# FilterBoard_Schematic.net
KiCad netlist of a schematic drawn in Altium Designer
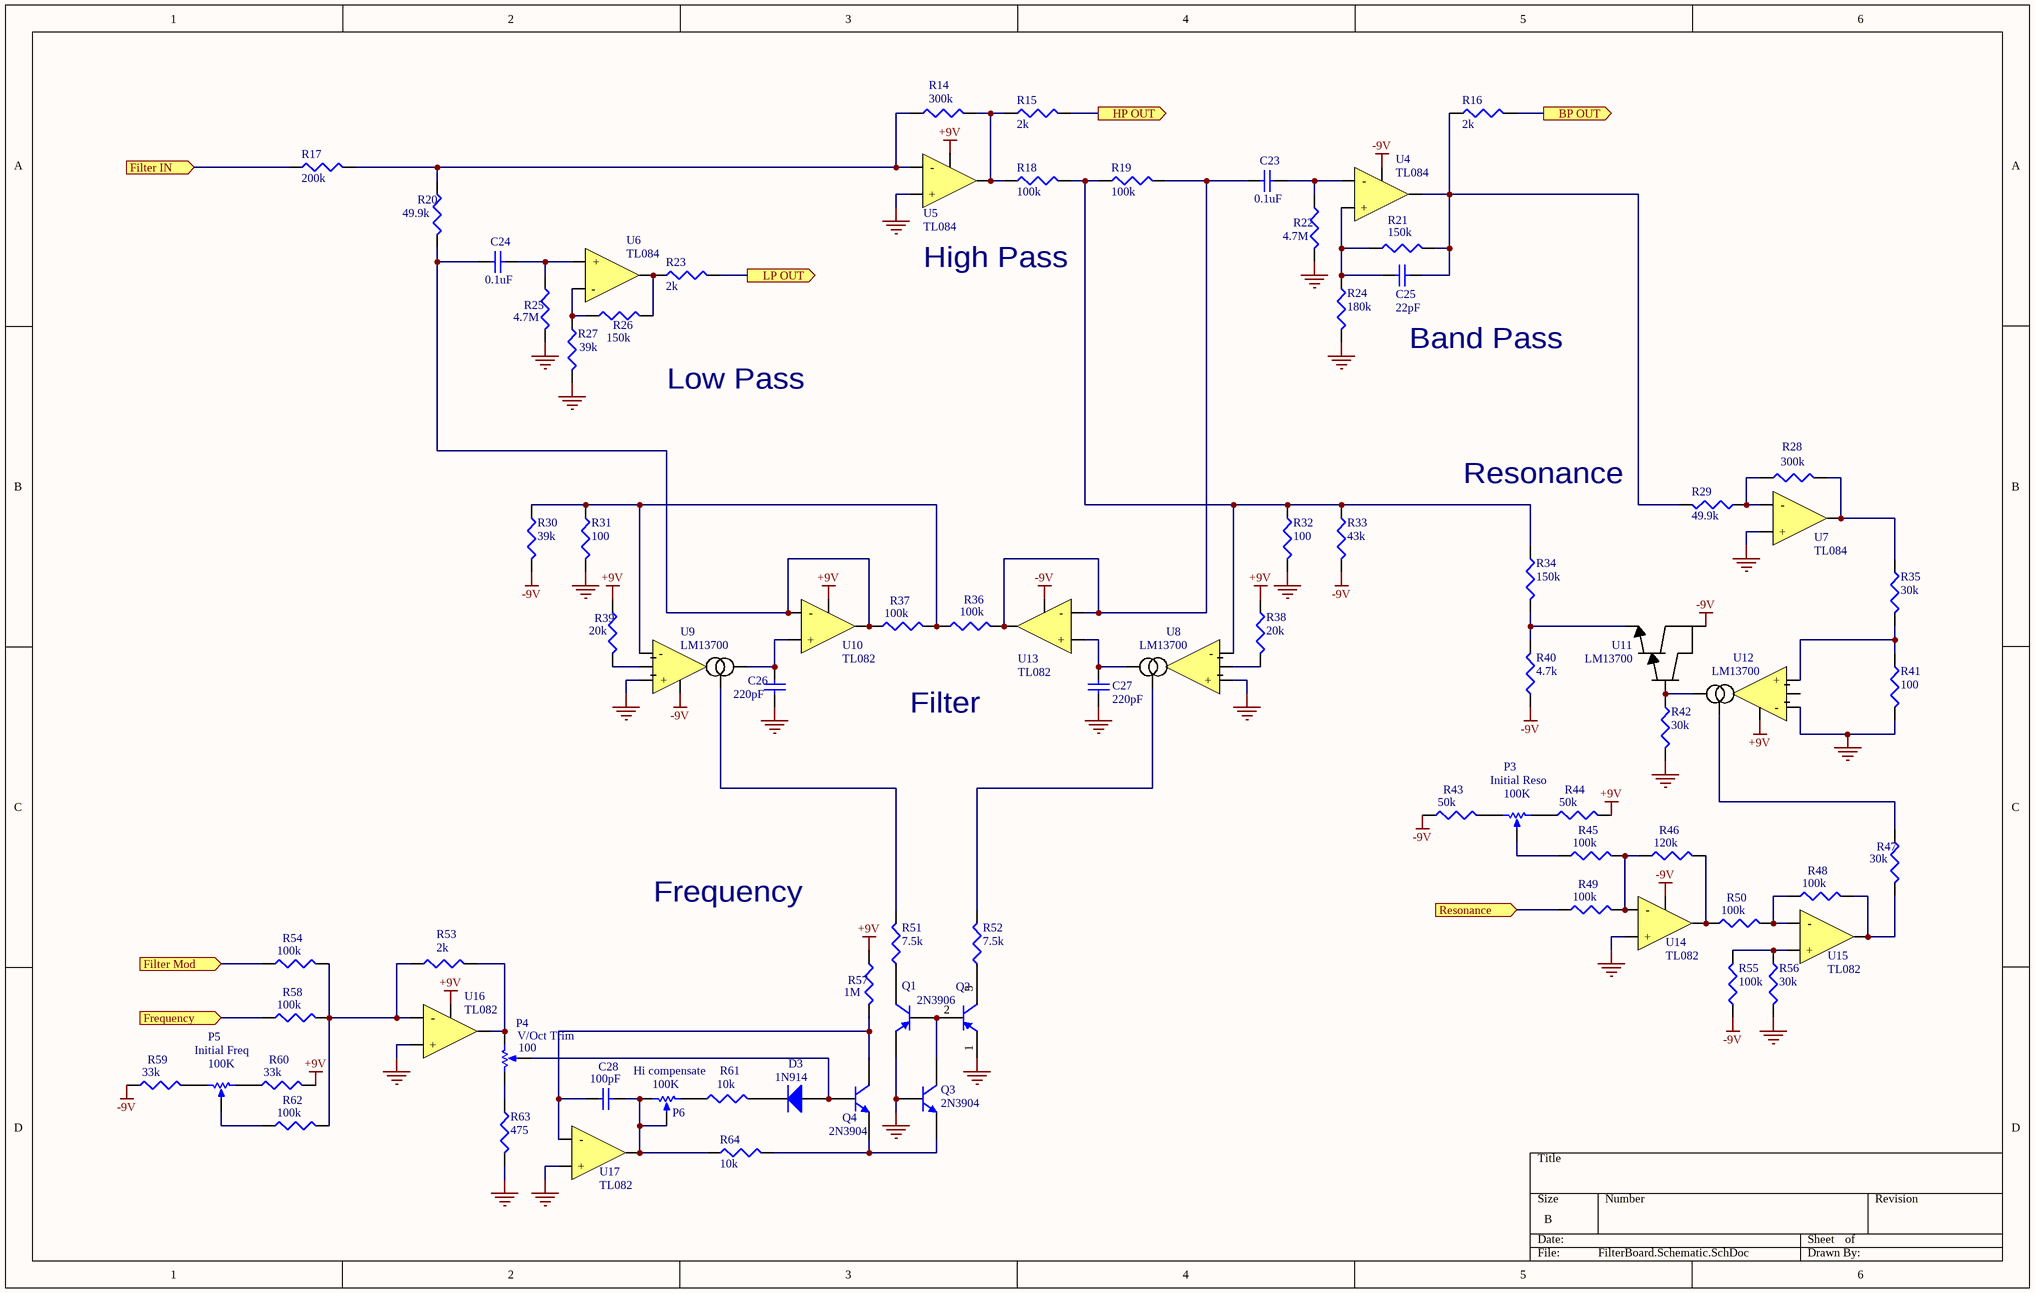
[diagram p0: FilterBoard.Schematic.SchDoc]

(export (version "E")
  (design (tool "Eeschema 10.0.6"))
  (components
    (comp (ref "C23")
      (value "0.1uF")
      (footprint "CAPC1608N")
      (description "Capacitor (Semiconductor SIM Model)")
      (fields (field (name "PUBLISHER") "Altium Limited"))
      (libsource (lib "Miscellaneous Devices") (part "Cap Semi"))
    )
    (comp (ref "C24")
      (value "0.1uF")
      (footprint "CAPC1608N")
      (description "Capacitor (Semiconductor SIM Model)")
      (fields (field (name "PUBLISHER") "Altium Limited"))
      (libsource (lib "Miscellaneous Devices") (part "Cap Semi"))
    )
    (comp (ref "C25")
      (value "22pF")
      (footprint "CAPC1608N")
      (description "Capacitor (Semiconductor SIM Model)")
      (fields (field (name "PUBLISHER") "Altium Limited"))
      (libsource (lib "Miscellaneous Devices") (part "Cap Semi"))
    )
    (comp (ref "C26")
      (value "220pF")
      (footprint "CAPC1608N")
      (description "Capacitor (Semiconductor SIM Model)")
      (fields (field (name "PUBLISHER") "Altium Limited"))
      (libsource (lib "Miscellaneous Devices") (part "Cap Semi"))
    )
    (comp (ref "C27")
      (value "220pF")
      (footprint "CAPC1608N")
      (description "Capacitor (Semiconductor SIM Model)")
      (fields (field (name "PUBLISHER") "Altium Limited"))
      (libsource (lib "Miscellaneous Devices") (part "Cap Semi"))
    )
    (comp (ref "C28")
      (value "100pF")
      (footprint "CAPC1608N")
      (description "Capacitor (Semiconductor SIM Model)")
      (fields (field (name "PUBLISHER") "Altium Limited"))
      (libsource (lib "Miscellaneous Devices") (part "Cap Semi"))
    )
    (comp (ref "D3")
      (value "1N914")
      (footprint "1N914")
      (description "1 Amp General Purpose Rectifier")
      (fields (field (name "PUBLISHER") "Altium Limited"))
      (libsource (lib "Miscellaneous Devices") (part "Diode 1N4001"))
    )
    (comp (ref "P3")
      (value "Initial Reso")
      (footprint "BOURNS Trim pot")
      (description "Potentiometer")
      (fields (field (name "ALTIUM_VALUE") "100K") (field (name "PUBLISHER") "Altium Limited"))
      (libsource (lib "Miscellaneous Devices") (part "RPot"))
    )
    (comp (ref "P4")
      (value "V/Oct Trim")
      (footprint "BOURNS Trim pot")
      (description "Potentiometer")
      (fields (field (name "ALTIUM_VALUE") "100") (field (name "PUBLISHER") "Altium Limited"))
      (libsource (lib "Miscellaneous Devices") (part "RPot"))
    )
    (comp (ref "P5")
      (value "Initial Freq")
      (footprint "BOURNS Trim pot")
      (description "Potentiometer")
      (fields (field (name "ALTIUM_VALUE") "100K") (field (name "PUBLISHER") "Altium Limited"))
      (libsource (lib "Miscellaneous Devices") (part "RPot"))
    )
    (comp (ref "P6")
      (value "Hi compensate")
      (footprint "BOURNS Trim pot")
      (description "Potentiometer")
      (fields (field (name "ALTIUM_VALUE") "100K") (field (name "PUBLISHER") "Altium Limited"))
      (libsource (lib "Miscellaneous Devices") (part "RPot"))
    )
    (comp (ref "Q1")
      (value "2N3906")
      (footprint "2N3906")
      (description "PNP General Purpose Amplifier")
      (fields (field (name "PUBLISHER") "Altium Limited"))
      (libsource (lib "Miscellaneous Devices") (part "2N3906"))
    )
    (comp (ref "Q2")
      (value "2N3906")
      (footprint "2N3906")
      (description "PNP General Purpose Amplifier")
      (fields (field (name "PUBLISHER") "Altium Limited"))
      (libsource (lib "") (part "2N3906_1"))
    )
    (comp (ref "Q3")
      (value "2N3904")
      (footprint "2N3906")
      (description "NPN General Purpose Amplifier")
      (fields (field (name "PUBLISHER") "Altium Limited"))
      (libsource (lib "Miscellaneous Devices") (part "2N3904"))
    )
    (comp (ref "Q4")
      (value "2N3904")
      (footprint "2N3906")
      (description "NPN General Purpose Amplifier")
      (fields (field (name "PUBLISHER") "Altium Limited"))
      (libsource (lib "Miscellaneous Devices") (part "2N3904"))
    )
    (comp (ref "R14")
      (value "300k")
      (footprint "CAPC1608N")
      (description "Resistor")
      (fields (field (name "PUBLISHER") "Altium Limited"))
      (libsource (lib "Miscellaneous Devices") (part "Res3"))
    )
    (comp (ref "R15")
      (value "2k")
      (footprint "CAPC1608N")
      (description "Resistor")
      (fields (field (name "PUBLISHER") "Altium Limited"))
      (libsource (lib "Miscellaneous Devices") (part "Res3"))
    )
    (comp (ref "R16")
      (value "2k")
      (footprint "CAPC1608N")
      (description "Resistor")
      (fields (field (name "PUBLISHER") "Altium Limited"))
      (libsource (lib "Miscellaneous Devices") (part "Res3"))
    )
    (comp (ref "R17")
      (value "200k")
      (footprint "CAPC1608N")
      (description "Resistor")
      (fields (field (name "PUBLISHER") "Altium Limited"))
      (libsource (lib "Miscellaneous Devices") (part "Res3"))
    )
    (comp (ref "R18")
      (value "100k")
      (footprint "CAPC1608N")
      (description "Resistor")
      (fields (field (name "PUBLISHER") "Altium Limited"))
      (libsource (lib "Miscellaneous Devices") (part "Res3"))
    )
    (comp (ref "R19")
      (value "100k")
      (footprint "CAPC1608N")
      (description "Resistor")
      (fields (field (name "PUBLISHER") "Altium Limited"))
      (libsource (lib "Miscellaneous Devices") (part "Res3"))
    )
    (comp (ref "R20")
      (value "49.9k")
      (footprint "CAPC1608N")
      (description "Resistor")
      (fields (field (name "PUBLISHER") "Altium Limited"))
      (libsource (lib "Miscellaneous Devices") (part "Res3"))
    )
    (comp (ref "R21")
      (value "150k")
      (footprint "CAPC1608N")
      (description "Resistor")
      (fields (field (name "PUBLISHER") "Altium Limited"))
      (libsource (lib "Miscellaneous Devices") (part "Res3"))
    )
    (comp (ref "R22")
      (value "4.7M")
      (footprint "CAPC1608N")
      (description "Resistor")
      (fields (field (name "PUBLISHER") "Altium Limited"))
      (libsource (lib "Miscellaneous Devices") (part "Res3"))
    )
    (comp (ref "R23")
      (value "2k")
      (footprint "CAPC1608N")
      (description "Resistor")
      (fields (field (name "PUBLISHER") "Altium Limited"))
      (libsource (lib "Miscellaneous Devices") (part "Res3"))
    )
    (comp (ref "R24")
      (value "180k")
      (footprint "CAPC1608N")
      (description "Resistor")
      (fields (field (name "PUBLISHER") "Altium Limited"))
      (libsource (lib "Miscellaneous Devices") (part "Res3"))
    )
    (comp (ref "R25")
      (value "4.7M")
      (footprint "CAPC1608N")
      (description "Resistor")
      (fields (field (name "PUBLISHER") "Altium Limited"))
      (libsource (lib "Miscellaneous Devices") (part "Res3"))
    )
    (comp (ref "R26")
      (value "150k")
      (footprint "CAPC1608N")
      (description "Resistor")
      (fields (field (name "PUBLISHER") "Altium Limited"))
      (libsource (lib "Miscellaneous Devices") (part "Res3"))
    )
    (comp (ref "R27")
      (value "39k")
      (footprint "CAPC1608N")
      (description "Resistor")
      (fields (field (name "PUBLISHER") "Altium Limited"))
      (libsource (lib "Miscellaneous Devices") (part "Res3"))
    )
    (comp (ref "R28")
      (value "300k")
      (footprint "CAPC1608N")
      (description "Resistor")
      (fields (field (name "PUBLISHER") "Altium Limited"))
      (libsource (lib "Miscellaneous Devices") (part "Res3"))
    )
    (comp (ref "R29")
      (value "49.9k")
      (footprint "CAPC1608N")
      (description "Resistor")
      (fields (field (name "PUBLISHER") "Altium Limited"))
      (libsource (lib "Miscellaneous Devices") (part "Res3"))
    )
    (comp (ref "R30")
      (value "39k")
      (footprint "CAPC1608N")
      (description "Resistor")
      (fields (field (name "PUBLISHER") "Altium Limited"))
      (libsource (lib "Miscellaneous Devices") (part "Res3"))
    )
    (comp (ref "R31")
      (value "100")
      (footprint "CAPC1608N")
      (description "Resistor")
      (fields (field (name "PUBLISHER") "Altium Limited"))
      (libsource (lib "Miscellaneous Devices") (part "Res3"))
    )
    (comp (ref "R32")
      (value "100")
      (footprint "CAPC1608N")
      (description "Resistor")
      (fields (field (name "PUBLISHER") "Altium Limited"))
      (libsource (lib "Miscellaneous Devices") (part "Res3"))
    )
    (comp (ref "R33")
      (value "43k")
      (footprint "CAPC1608N")
      (description "Resistor")
      (fields (field (name "PUBLISHER") "Altium Limited"))
      (libsource (lib "Miscellaneous Devices") (part "Res3"))
    )
    (comp (ref "R34")
      (value "150k")
      (footprint "CAPC1608N")
      (description "Resistor")
      (fields (field (name "PUBLISHER") "Altium Limited"))
      (libsource (lib "Miscellaneous Devices") (part "Res3"))
    )
    (comp (ref "R35")
      (value "30k")
      (footprint "CAPC1608N")
      (description "Resistor")
      (fields (field (name "PUBLISHER") "Altium Limited"))
      (libsource (lib "Miscellaneous Devices") (part "Res3"))
    )
    (comp (ref "R36")
      (value "100k")
      (footprint "CAPC1608N")
      (description "Resistor")
      (fields (field (name "PUBLISHER") "Altium Limited"))
      (libsource (lib "Miscellaneous Devices") (part "Res3"))
    )
    (comp (ref "R37")
      (value "100k")
      (footprint "CAPC1608N")
      (description "Resistor")
      (fields (field (name "PUBLISHER") "Altium Limited"))
      (libsource (lib "Miscellaneous Devices") (part "Res3"))
    )
    (comp (ref "R38")
      (value "20k")
      (footprint "CAPC1608N")
      (description "Resistor")
      (fields (field (name "PUBLISHER") "Altium Limited"))
      (libsource (lib "Miscellaneous Devices") (part "Res3"))
    )
    (comp (ref "R39")
      (value "20k")
      (footprint "CAPC1608N")
      (description "Resistor")
      (fields (field (name "PUBLISHER") "Altium Limited"))
      (libsource (lib "Miscellaneous Devices") (part "Res3"))
    )
    (comp (ref "R40")
      (value "4.7k")
      (footprint "CAPC1608N")
      (description "Resistor")
      (fields (field (name "PUBLISHER") "Altium Limited"))
      (libsource (lib "Miscellaneous Devices") (part "Res3"))
    )
    (comp (ref "R41")
      (value "100")
      (footprint "CAPC1608N")
      (description "Resistor")
      (fields (field (name "PUBLISHER") "Altium Limited"))
      (libsource (lib "Miscellaneous Devices") (part "Res3"))
    )
    (comp (ref "R42")
      (value "30k")
      (footprint "CAPC1608N")
      (description "Resistor")
      (fields (field (name "PUBLISHER") "Altium Limited"))
      (libsource (lib "Miscellaneous Devices") (part "Res3"))
    )
    (comp (ref "R43")
      (value "50k")
      (footprint "CAPC1608N")
      (description "Resistor")
      (fields (field (name "PUBLISHER") "Altium Limited"))
      (libsource (lib "Miscellaneous Devices") (part "Res3"))
    )
    (comp (ref "R44")
      (value "50k")
      (footprint "CAPC1608N")
      (description "Resistor")
      (fields (field (name "PUBLISHER") "Altium Limited"))
      (libsource (lib "Miscellaneous Devices") (part "Res3"))
    )
    (comp (ref "R45")
      (value "100k")
      (footprint "CAPC1608N")
      (description "Resistor")
      (fields (field (name "PUBLISHER") "Altium Limited"))
      (libsource (lib "Miscellaneous Devices") (part "Res3"))
    )
    (comp (ref "R46")
      (value "120k")
      (footprint "CAPC1608N")
      (description "Resistor")
      (fields (field (name "PUBLISHER") "Altium Limited"))
      (libsource (lib "Miscellaneous Devices") (part "Res3"))
    )
    (comp (ref "R47")
      (value "30k")
      (footprint "CAPC1608N")
      (description "Resistor")
      (fields (field (name "PUBLISHER") "Altium Limited"))
      (libsource (lib "Miscellaneous Devices") (part "Res3"))
    )
    (comp (ref "R48")
      (value "100k")
      (footprint "CAPC1608N")
      (description "Resistor")
      (fields (field (name "PUBLISHER") "Altium Limited"))
      (libsource (lib "Miscellaneous Devices") (part "Res3"))
    )
    (comp (ref "R49")
      (value "100k")
      (footprint "CAPC1608N")
      (description "Resistor")
      (fields (field (name "PUBLISHER") "Altium Limited"))
      (libsource (lib "Miscellaneous Devices") (part "Res3"))
    )
    (comp (ref "R50")
      (value "100k")
      (footprint "CAPC1608N")
      (description "Resistor")
      (fields (field (name "PUBLISHER") "Altium Limited"))
      (libsource (lib "Miscellaneous Devices") (part "Res3"))
    )
    (comp (ref "R51")
      (value "7.5k")
      (footprint "CAPC1608N")
      (description "Resistor")
      (fields (field (name "PUBLISHER") "Altium Limited"))
      (libsource (lib "Miscellaneous Devices") (part "Res3"))
    )
    (comp (ref "R52")
      (value "7.5k")
      (footprint "CAPC1608N")
      (description "Resistor")
      (fields (field (name "PUBLISHER") "Altium Limited"))
      (libsource (lib "Miscellaneous Devices") (part "Res3"))
    )
    (comp (ref "R53")
      (value "2k")
      (footprint "CAPC1608N")
      (description "Resistor")
      (fields (field (name "PUBLISHER") "Altium Limited"))
      (libsource (lib "Miscellaneous Devices") (part "Res3"))
    )
    (comp (ref "R54")
      (value "100k")
      (footprint "CAPC1608N")
      (description "Resistor")
      (fields (field (name "PUBLISHER") "Altium Limited"))
      (libsource (lib "Miscellaneous Devices") (part "Res3"))
    )
    (comp (ref "R55")
      (value "100k")
      (footprint "CAPC1608N")
      (description "Resistor")
      (fields (field (name "PUBLISHER") "Altium Limited"))
      (libsource (lib "Miscellaneous Devices") (part "Res3"))
    )
    (comp (ref "R56")
      (value "30k")
      (footprint "CAPC1608N")
      (description "Resistor")
      (fields (field (name "PUBLISHER") "Altium Limited"))
      (libsource (lib "Miscellaneous Devices") (part "Res3"))
    )
    (comp (ref "R57")
      (value "1M")
      (footprint "CAPC1608N")
      (description "Resistor")
      (fields (field (name "PUBLISHER") "Altium Limited"))
      (libsource (lib "Miscellaneous Devices") (part "Res3"))
    )
    (comp (ref "R58")
      (value "100k")
      (footprint "CAPC1608N")
      (description "Resistor")
      (fields (field (name "PUBLISHER") "Altium Limited"))
      (libsource (lib "Miscellaneous Devices") (part "Res3"))
    )
    (comp (ref "R59")
      (value "33k")
      (footprint "CAPC1608N")
      (description "Resistor")
      (fields (field (name "PUBLISHER") "Altium Limited"))
      (libsource (lib "Miscellaneous Devices") (part "Res3"))
    )
    (comp (ref "R60")
      (value "33k")
      (footprint "CAPC1608N")
      (description "Resistor")
      (fields (field (name "PUBLISHER") "Altium Limited"))
      (libsource (lib "Miscellaneous Devices") (part "Res3"))
    )
    (comp (ref "R61")
      (value "10k")
      (footprint "CAPC1608N")
      (description "Resistor")
      (fields (field (name "PUBLISHER") "Altium Limited"))
      (libsource (lib "Miscellaneous Devices") (part "Res3"))
    )
    (comp (ref "R62")
      (value "100k")
      (footprint "CAPC1608N")
      (description "Resistor")
      (fields (field (name "PUBLISHER") "Altium Limited"))
      (libsource (lib "Miscellaneous Devices") (part "Res3"))
    )
    (comp (ref "R63")
      (value "475")
      (footprint "CAPC1608N")
      (description "Resistor")
      (fields (field (name "PUBLISHER") "Altium Limited"))
      (libsource (lib "Miscellaneous Devices") (part "Res3"))
    )
    (comp (ref "R64")
      (value "10k")
      (footprint "CAPC1608N")
      (description "Resistor")
      (fields (field (name "PUBLISHER") "Altium Limited"))
      (libsource (lib "Miscellaneous Devices") (part "Res3"))
    )
    (comp (ref "U4")
      (value "TL084")
      (footprint "TL084_3PADS+ALIM")
      (libsource (lib "SynthyTwo.Components") (part "TL084"))
    )
    (comp (ref "U5")
      (value "TL084")
      (footprint "TL084_3PADS+ALIM")
      (libsource (lib "SynthyTwo.Components") (part "TL084"))
    )
    (comp (ref "U6") (value "TL084") (footprint "TL084_3PADS") (libsource (lib "") (part "TL084_1")))
    (comp (ref "U7") (value "TL084") (footprint "TL084_3PADS") (libsource (lib "") (part "TL084_2")))
    (comp (ref "U8")
      (value "LM13700")
      (footprint "LM13700_5PADS")
      (libsource (lib "SynthyTwo.Components") (part "LM13700_2"))
    )
    (comp (ref "U9")
      (value "LM13700")
      (footprint "LM13700_5PADS+ALIM")
      (libsource (lib "SynthyTwo.Components") (part "LM13700"))
    )
    (comp (ref "U10")
      (value "TL082")
      (footprint "TL084_3PADS+ALIM")
      (libsource (lib "SynthyTwo.Components") (part "TL082"))
    )
    (comp (ref "U11")
      (value "LM13700")
      (footprint "LM13700_3PADS")
      (libsource (lib "SynthyTwo.Components") (part "LM13700_1"))
    )
    (comp (ref "U12")
      (value "LM13700")
      (footprint "LM13700_5PADS+ALIM")
      (libsource (lib "SynthyTwo.Components") (part "LM13700"))
    )
    (comp (ref "U13")
      (value "TL082")
      (footprint "TL084_3PADS+ALIM")
      (libsource (lib "SynthyTwo.Components") (part "TL082"))
    )
    (comp (ref "U14")
      (value "TL082")
      (footprint "TL084_3PADS+ALIM")
      (libsource (lib "SynthyTwo.Components") (part "TL082"))
    )
    (comp (ref "U15") (value "TL082") (footprint "TL084_3PADS") (libsource (lib "") (part "TL082_1")))
    (comp (ref "U16")
      (value "TL082")
      (footprint "TL084_3PADS+ALIM")
      (libsource (lib "SynthyTwo.Components") (part "TL082"))
    )
    (comp (ref "U17") (value "TL082") (footprint "TL084_3PADS") (libsource (lib "") (part "TL082_1")))
  )
  (nets
    (net (code "1") (name "+9V") (class "Default")
      (node (ref "R38") (pin "1") (pinfunction "1_1") (pintype "passive"))
      (node (ref "R39") (pin "1") (pinfunction "1_1") (pintype "passive"))
      (node (ref "R44") (pin "2") (pinfunction "2_2") (pintype "passive"))
      (node (ref "R57") (pin "1") (pinfunction "1_1") (pintype "passive"))
      (node (ref "R60") (pin "2") (pinfunction "2_2") (pintype "passive"))
      (node (ref "U10") (pin "4") (pinfunction "VCC+_4") (pintype "passive"))
      (node (ref "U12") (pin "6") (pinfunction "VCC-_6") (pintype "passive"))
      (node (ref "U16") (pin "4") (pinfunction "VCC+_4") (pintype "passive"))
      (node (ref "U5") (pin "4") (pinfunction "VCC+_4") (pintype "passive"))
    )
    (net (code "2") (name "-9V") (class "Default")
      (node (ref "R30") (pin "2") (pinfunction "2_2") (pintype "passive"))
      (node (ref "R33") (pin "2") (pinfunction "2_2") (pintype "passive"))
      (node (ref "R40") (pin "1") (pinfunction "1_1") (pintype "passive"))
      (node (ref "R43") (pin "1") (pinfunction "1_1") (pintype "passive"))
      (node (ref "R55") (pin "1") (pinfunction "1_1") (pintype "passive"))
      (node (ref "R59") (pin "1") (pinfunction "1_1") (pintype "passive"))
      (node (ref "U11") (pin "1") (pinfunction "V+_1") (pintype "passive"))
      (node (ref "U13") (pin "4") (pinfunction "VCC+_4") (pintype "passive"))
      (node (ref "U14") (pin "4") (pinfunction "VCC+_4") (pintype "passive"))
      (node (ref "U4") (pin "4") (pinfunction "VCC+_4") (pintype "passive"))
      (node (ref "U9") (pin "6") (pinfunction "VCC-_6") (pintype "passive"))
    )
    (net (code "3") (name "/BP OUT") (class "Default")
      (node (ref "R16") (pin "2") (pinfunction "2_2") (pintype "passive"))
    )
    (net (code "4") (name "/Filter IN") (class "Default")
      (node (ref "R17") (pin "1") (pinfunction "1_1") (pintype "passive"))
    )
    (net (code "5") (name "/Filter Mod") (class "Default")
      (node (ref "R54") (pin "1") (pinfunction "1_1") (pintype "passive"))
    )
    (net (code "6") (name "/Frequency") (class "Default")
      (node (ref "R58") (pin "1") (pinfunction "1_1") (pintype "passive"))
    )
    (net (code "7") (name "/HP OUT") (class "Default")
      (node (ref "R15") (pin "2") (pinfunction "2_2") (pintype "passive"))
    )
    (net (code "8") (name "/LP OUT") (class "Default")
      (node (ref "R23") (pin "2") (pinfunction "2_2") (pintype "passive"))
    )
    (net (code "9") (name "/Resonance") (class "Default")
      (node (ref "R49") (pin "1") (pinfunction "1_1") (pintype "passive"))
    )
    (net (code "10") (name "GND") (class "Default")
      (node (ref "C26") (pin "1") (pinfunction "1_1") (pintype "passive"))
      (node (ref "C27") (pin "1") (pinfunction "1_1") (pintype "passive"))
      (node (ref "Q1") (pin "1") (pinfunction "E_1") (pintype "passive"))
      (node (ref "Q2") (pin "1") (pinfunction "E_1") (pintype "passive"))
      (node (ref "Q3") (pin "2") (pinfunction "B_2") (pintype "passive"))
      (node (ref "R22") (pin "2") (pinfunction "2_2") (pintype "passive"))
      (node (ref "R24") (pin "2") (pinfunction "2_2") (pintype "passive"))
      (node (ref "R25") (pin "2") (pinfunction "2_2") (pintype "passive"))
      (node (ref "R27") (pin "2") (pinfunction "2_2") (pintype "passive"))
      (node (ref "R31") (pin "2") (pinfunction "2_2") (pintype "passive"))
      (node (ref "R32") (pin "2") (pinfunction "2_2") (pintype "passive"))
      (node (ref "R41") (pin "2") (pinfunction "2_2") (pintype "passive"))
      (node (ref "R42") (pin "2") (pinfunction "2_2") (pintype "passive"))
      (node (ref "R56") (pin "2") (pinfunction "2_2") (pintype "passive"))
      (node (ref "R63") (pin "2") (pinfunction "2_2") (pintype "passive"))
      (node (ref "U12") (pin "3") (pinfunction "-_3") (pintype "passive"))
      (node (ref "U14") (pin "3") (pinfunction "+_3") (pintype "passive"))
      (node (ref "U16") (pin "3") (pinfunction "+_3") (pintype "passive"))
      (node (ref "U17") (pin "3") (pinfunction "+_3") (pintype "passive"))
      (node (ref "U5") (pin "3") (pinfunction "+_3") (pintype "passive"))
      (node (ref "U7") (pin "3") (pinfunction "+_3") (pintype "passive"))
      (node (ref "U8") (pin "3") (pinfunction "+_3") (pintype "passive"))
      (node (ref "U9") (pin "3") (pinfunction "-_3") (pintype "passive"))
    )
    (net (code "11") (name "Net-(D3-A)") (class "Default")
      (node (ref "D3") (pin "1") (pinfunction "A_1") (pintype "passive"))
      (node (ref "P4") (pin "3") (pinfunction "TAP_3") (pintype "passive"))
      (node (ref "Q4") (pin "2") (pinfunction "B_2") (pintype "passive"))
    )
    (net (code "12") (name "Net-(D3-K)") (class "Default")
      (node (ref "D3") (pin "2") (pinfunction "K_2") (pintype "passive"))
      (node (ref "R61") (pin "2") (pinfunction "2_2") (pintype "passive"))
    )
    (net (code "13") (name "Net-(P3-BOT)") (class "Default")
      (node (ref "P3") (pin "2") (pinfunction "BOT_2") (pintype "passive"))
      (node (ref "R43") (pin "2") (pinfunction "2_2") (pintype "passive"))
    )
    (net (code "14") (name "Net-(P3-TAP)") (class "Default")
      (node (ref "P3") (pin "3") (pinfunction "TAP_3") (pintype "passive"))
      (node (ref "R45") (pin "1") (pinfunction "1_1") (pintype "passive"))
    )
    (net (code "15") (name "Net-(P3-TOP)") (class "Default")
      (node (ref "P3") (pin "1") (pinfunction "TOP_1") (pintype "passive"))
      (node (ref "R44") (pin "1") (pinfunction "1_1") (pintype "passive"))
    )
    (net (code "16") (name "Net-(P4-BOT)") (class "Default")
      (node (ref "P4") (pin "2") (pinfunction "BOT_2") (pintype "passive"))
      (node (ref "R63") (pin "1") (pinfunction "1_1") (pintype "passive"))
    )
    (net (code "17") (name "Net-(P4-TOP)") (class "Default")
      (node (ref "P4") (pin "1") (pinfunction "TOP_1") (pintype "passive"))
      (node (ref "R53") (pin "2") (pinfunction "2_2") (pintype "passive"))
      (node (ref "U16") (pin "1") (pinfunction "OUT_1") (pintype "passive"))
    )
    (net (code "18") (name "Net-(P5-BOT)") (class "Default")
      (node (ref "P5") (pin "2") (pinfunction "BOT_2") (pintype "passive"))
      (node (ref "R59") (pin "2") (pinfunction "2_2") (pintype "passive"))
    )
    (net (code "19") (name "Net-(P5-TAP)") (class "Default")
      (node (ref "P5") (pin "3") (pinfunction "TAP_3") (pintype "passive"))
      (node (ref "R62") (pin "1") (pinfunction "1_1") (pintype "passive"))
    )
    (net (code "20") (name "Net-(P5-TOP)") (class "Default")
      (node (ref "P5") (pin "1") (pinfunction "TOP_1") (pintype "passive"))
      (node (ref "R60") (pin "1") (pinfunction "1_1") (pintype "passive"))
    )
    (net (code "21") (name "Net-(P6-BOT)") (class "Default")
      (node (ref "C28") (pin "2") (pinfunction "2_2") (pintype "passive"))
      (node (ref "P6") (pin "2") (pinfunction "BOT_2") (pintype "passive"))
      (node (ref "P6") (pin "3") (pinfunction "TAP_3") (pintype "passive"))
      (node (ref "R64") (pin "1") (pinfunction "1_1") (pintype "passive"))
      (node (ref "U17") (pin "1") (pinfunction "OUT_1") (pintype "passive"))
    )
    (net (code "22") (name "Net-(P6-TOP)") (class "Default")
      (node (ref "P6") (pin "1") (pinfunction "TOP_1") (pintype "passive"))
      (node (ref "R61") (pin "1") (pinfunction "1_1") (pintype "passive"))
    )
    (net (code "23") (name "Net-(Q1-B)") (class "Default")
      (node (ref "Q1") (pin "2") (pinfunction "B_2") (pintype "passive"))
      (node (ref "Q2") (pin "2") (pinfunction "B_2") (pintype "passive"))
      (node (ref "Q3") (pin "3") (pinfunction "C_3") (pintype "passive"))
    )
    (net (code "24") (name "Net-(Q1-C)") (class "Default")
      (node (ref "Q1") (pin "3") (pinfunction "C_3") (pintype "passive"))
      (node (ref "R51") (pin "1") (pinfunction "1_1") (pintype "passive"))
    )
    (net (code "25") (name "Net-(Q2-C)") (class "Default")
      (node (ref "Q2") (pin "3") (pinfunction "C_3") (pintype "passive"))
      (node (ref "R52") (pin "1") (pinfunction "1_1") (pintype "passive"))
    )
    (net (code "26") (name "Net-(Q3-E)") (class "Default")
      (node (ref "Q3") (pin "1") (pinfunction "E_1") (pintype "passive"))
      (node (ref "Q4") (pin "1") (pinfunction "E_1") (pintype "passive"))
      (node (ref "R64") (pin "2") (pinfunction "2_2") (pintype "passive"))
    )
    (net (code "27") (name "Net-(Q4-C)") (class "Default")
      (node (ref "C28") (pin "1") (pinfunction "1_1") (pintype "passive"))
      (node (ref "Q4") (pin "3") (pinfunction "C_3") (pintype "passive"))
      (node (ref "R57") (pin "2") (pinfunction "2_2") (pintype "passive"))
      (node (ref "U17") (pin "2") (pinfunction "-_2") (pintype "passive"))
    )
    (net (code "28") (name "Net-(R38-Pad2)") (class "Default")
      (node (ref "R38") (pin "2") (pinfunction "2_2") (pintype "passive"))
      (node (ref "U8") (pin "2") (pinfunction "2_2") (pintype "passive"))
    )
    (net (code "29") (name "Net-(R39-Pad2)") (class "Default")
      (node (ref "R39") (pin "2") (pinfunction "2_2") (pintype "passive"))
      (node (ref "U9") (pin "2") (pinfunction "2_2") (pintype "passive"))
    )
    (net (code "30") (name "Net-(U4-+)") (class "Default")
      (node (ref "C25") (pin "1") (pinfunction "1_1") (pintype "passive"))
      (node (ref "R21") (pin "1") (pinfunction "1_1") (pintype "passive"))
      (node (ref "R24") (pin "1") (pinfunction "1_1") (pintype "passive"))
      (node (ref "U4") (pin "3") (pinfunction "+_3") (pintype "passive"))
    )
    (net (code "31") (name "Net-(U4--)") (class "Default")
      (node (ref "C23") (pin "2") (pinfunction "2_2") (pintype "passive"))
      (node (ref "R22") (pin "1") (pinfunction "1_1") (pintype "passive"))
      (node (ref "U4") (pin "2") (pinfunction "-_2") (pintype "passive"))
    )
    (net (code "32") (name "Net-(U4-OUT)") (class "Default")
      (node (ref "C25") (pin "2") (pinfunction "2_2") (pintype "passive"))
      (node (ref "R16") (pin "1") (pinfunction "1_1") (pintype "passive"))
      (node (ref "R21") (pin "2") (pinfunction "2_2") (pintype "passive"))
      (node (ref "R29") (pin "2") (pinfunction "2_2") (pintype "passive"))
      (node (ref "U4") (pin "1") (pinfunction "OUT_1") (pintype "passive"))
    )
    (net (code "33") (name "Net-(U5--)") (class "Default")
      (node (ref "R14") (pin "1") (pinfunction "1_1") (pintype "passive"))
      (node (ref "R17") (pin "2") (pinfunction "2_2") (pintype "passive"))
      (node (ref "R20") (pin "1") (pinfunction "1_1") (pintype "passive"))
      (node (ref "U5") (pin "2") (pinfunction "-_2") (pintype "passive"))
    )
    (net (code "34") (name "Net-(U5-OUT)") (class "Default")
      (node (ref "R14") (pin "2") (pinfunction "2_2") (pintype "passive"))
      (node (ref "R15") (pin "1") (pinfunction "1_1") (pintype "passive"))
      (node (ref "R18") (pin "1") (pinfunction "1_1") (pintype "passive"))
      (node (ref "U5") (pin "1") (pinfunction "OUT_1") (pintype "passive"))
    )
    (net (code "35") (name "Net-(U6-+)") (class "Default")
      (node (ref "C24") (pin "2") (pinfunction "2_2") (pintype "passive"))
      (node (ref "R25") (pin "1") (pinfunction "1_1") (pintype "passive"))
      (node (ref "U6") (pin "3") (pinfunction "+_3") (pintype "passive"))
    )
    (net (code "36") (name "Net-(U6--)") (class "Default")
      (node (ref "R26") (pin "1") (pinfunction "1_1") (pintype "passive"))
      (node (ref "R27") (pin "1") (pinfunction "1_1") (pintype "passive"))
      (node (ref "U6") (pin "2") (pinfunction "-_2") (pintype "passive"))
    )
    (net (code "37") (name "Net-(U6-OUT)") (class "Default")
      (node (ref "R23") (pin "1") (pinfunction "1_1") (pintype "passive"))
      (node (ref "R26") (pin "2") (pinfunction "2_2") (pintype "passive"))
      (node (ref "U6") (pin "1") (pinfunction "OUT_1") (pintype "passive"))
    )
    (net (code "38") (name "Net-(U7--)") (class "Default")
      (node (ref "R28") (pin "1") (pinfunction "1_1") (pintype "passive"))
      (node (ref "R29") (pin "1") (pinfunction "1_1") (pintype "passive"))
      (node (ref "U7") (pin "2") (pinfunction "-_2") (pintype "passive"))
    )
    (net (code "39") (name "Net-(U7-OUT)") (class "Default")
      (node (ref "R28") (pin "2") (pinfunction "2_2") (pintype "passive"))
      (node (ref "R35") (pin "1") (pinfunction "1_1") (pintype "passive"))
      (node (ref "U7") (pin "1") (pinfunction "OUT_1") (pintype "passive"))
    )
    (net (code "40") (name "Net-(U8--)") (class "Default")
      (node (ref "R18") (pin "2") (pinfunction "2_2") (pintype "passive"))
      (node (ref "R19") (pin "1") (pinfunction "1_1") (pintype "passive"))
      (node (ref "R32") (pin "1") (pinfunction "1_1") (pintype "passive"))
      (node (ref "R33") (pin "1") (pinfunction "1_1") (pintype "passive"))
      (node (ref "R34") (pin "1") (pinfunction "1_1") (pintype "passive"))
      (node (ref "U8") (pin "4") (pinfunction "-_4") (pintype "passive"))
    )
    (net (code "41") (name "Net-(U8-BIAS)") (class "Default")
      (node (ref "R52") (pin "2") (pinfunction "2_2") (pintype "passive"))
      (node (ref "U8") (pin "1") (pinfunction "BIAS_1") (pintype "passive"))
    )
    (net (code "42") (name "Net-(U9-+)") (class "Default")
      (node (ref "R30") (pin "1") (pinfunction "1_1") (pintype "passive"))
      (node (ref "R31") (pin "1") (pinfunction "1_1") (pintype "passive"))
      (node (ref "R36") (pin "1") (pinfunction "1_1") (pintype "passive"))
      (node (ref "R37") (pin "2") (pinfunction "2_2") (pintype "passive"))
      (node (ref "U9") (pin "4") (pinfunction "+_4") (pintype "passive"))
    )
    (net (code "43") (name "Net-(U9-BIAS)") (class "Default")
      (node (ref "R51") (pin "2") (pinfunction "2_2") (pintype "passive"))
      (node (ref "U9") (pin "1") (pinfunction "BIAS_1") (pintype "passive"))
    )
    (net (code "44") (name "Net-(U10-+)") (class "Default")
      (node (ref "C26") (pin "2") (pinfunction "2_2") (pintype "passive"))
      (node (ref "U10") (pin "3") (pinfunction "+_3") (pintype "passive"))
      (node (ref "U9") (pin "5") (pinfunction "OUT_5") (pintype "passive"))
    )
    (net (code "45") (name "Net-(U10--)") (class "Default")
      (node (ref "C24") (pin "1") (pinfunction "1_1") (pintype "passive"))
      (node (ref "R20") (pin "2") (pinfunction "2_2") (pintype "passive"))
      (node (ref "R37") (pin "1") (pinfunction "1_1") (pintype "passive"))
      (node (ref "U10") (pin "1") (pinfunction "OUT_1") (pintype "passive"))
      (node (ref "U10") (pin "2") (pinfunction "-_2") (pintype "passive"))
    )
    (net (code "46") (name "Net-(U11-BIN)") (class "Default")
      (node (ref "R42") (pin "1") (pinfunction "1_1") (pintype "passive"))
      (node (ref "U11") (pin "2") (pinfunction "BIN_2") (pintype "passive"))
      (node (ref "U12") (pin "5") (pinfunction "OUT_5") (pintype "passive"))
    )
    (net (code "47") (name "Net-(U11-BOUT)") (class "Default")
      (node (ref "R34") (pin "2") (pinfunction "2_2") (pintype "passive"))
      (node (ref "R40") (pin "2") (pinfunction "2_2") (pintype "passive"))
      (node (ref "U11") (pin "3") (pinfunction "BOUT_3") (pintype "passive"))
    )
    (net (code "48") (name "Net-(U12-+)") (class "Default")
      (node (ref "R35") (pin "2") (pinfunction "2_2") (pintype "passive"))
      (node (ref "R41") (pin "1") (pinfunction "1_1") (pintype "passive"))
      (node (ref "U12") (pin "4") (pinfunction "+_4") (pintype "passive"))
    )
    (net (code "49") (name "Net-(U12-BIAS)") (class "Default")
      (node (ref "R47") (pin "1") (pinfunction "1_1") (pintype "passive"))
      (node (ref "U12") (pin "1") (pinfunction "BIAS_1") (pintype "passive"))
    )
    (net (code "50") (name "Net-(U13-+)") (class "Default")
      (node (ref "C27") (pin "2") (pinfunction "2_2") (pintype "passive"))
      (node (ref "U13") (pin "3") (pinfunction "+_3") (pintype "passive"))
      (node (ref "U8") (pin "5") (pinfunction "OUT_5") (pintype "passive"))
    )
    (net (code "51") (name "Net-(U13--)") (class "Default")
      (node (ref "C23") (pin "1") (pinfunction "1_1") (pintype "passive"))
      (node (ref "R19") (pin "2") (pinfunction "2_2") (pintype "passive"))
      (node (ref "R36") (pin "2") (pinfunction "2_2") (pintype "passive"))
      (node (ref "U13") (pin "1") (pinfunction "OUT_1") (pintype "passive"))
      (node (ref "U13") (pin "2") (pinfunction "-_2") (pintype "passive"))
    )
    (net (code "52") (name "Net-(U14--)") (class "Default")
      (node (ref "R45") (pin "2") (pinfunction "2_2") (pintype "passive"))
      (node (ref "R46") (pin "1") (pinfunction "1_1") (pintype "passive"))
      (node (ref "R49") (pin "2") (pinfunction "2_2") (pintype "passive"))
      (node (ref "U14") (pin "2") (pinfunction "-_2") (pintype "passive"))
    )
    (net (code "53") (name "Net-(U14-OUT)") (class "Default")
      (node (ref "R46") (pin "2") (pinfunction "2_2") (pintype "passive"))
      (node (ref "R50") (pin "1") (pinfunction "1_1") (pintype "passive"))
      (node (ref "U14") (pin "1") (pinfunction "OUT_1") (pintype "passive"))
    )
    (net (code "54") (name "Net-(U15-+)") (class "Default")
      (node (ref "R55") (pin "2") (pinfunction "2_2") (pintype "passive"))
      (node (ref "R56") (pin "1") (pinfunction "1_1") (pintype "passive"))
      (node (ref "U15") (pin "3") (pinfunction "+_3") (pintype "passive"))
    )
    (net (code "55") (name "Net-(U15--)") (class "Default")
      (node (ref "R48") (pin "1") (pinfunction "1_1") (pintype "passive"))
      (node (ref "R50") (pin "2") (pinfunction "2_2") (pintype "passive"))
      (node (ref "U15") (pin "2") (pinfunction "-_2") (pintype "passive"))
    )
    (net (code "56") (name "Net-(U15-OUT)") (class "Default")
      (node (ref "R47") (pin "2") (pinfunction "2_2") (pintype "passive"))
      (node (ref "R48") (pin "2") (pinfunction "2_2") (pintype "passive"))
      (node (ref "U15") (pin "1") (pinfunction "OUT_1") (pintype "passive"))
    )
    (net (code "57") (name "Net-(U16--)") (class "Default")
      (node (ref "R53") (pin "1") (pinfunction "1_1") (pintype "passive"))
      (node (ref "R54") (pin "2") (pinfunction "2_2") (pintype "passive"))
      (node (ref "R58") (pin "2") (pinfunction "2_2") (pintype "passive"))
      (node (ref "R62") (pin "2") (pinfunction "2_2") (pintype "passive"))
      (node (ref "U16") (pin "2") (pinfunction "-_2") (pintype "passive"))
    )
    (net (code "58") (name "unconnected-(U12-Pad2)") (class "Default")
      (node (ref "U12") (pin "2") (pinfunction "2_2") (pintype "passive"))
    )
  )
)
